# saw_filter_pcb.net
KiCad netlist of a schematic drawn in Altium Designer
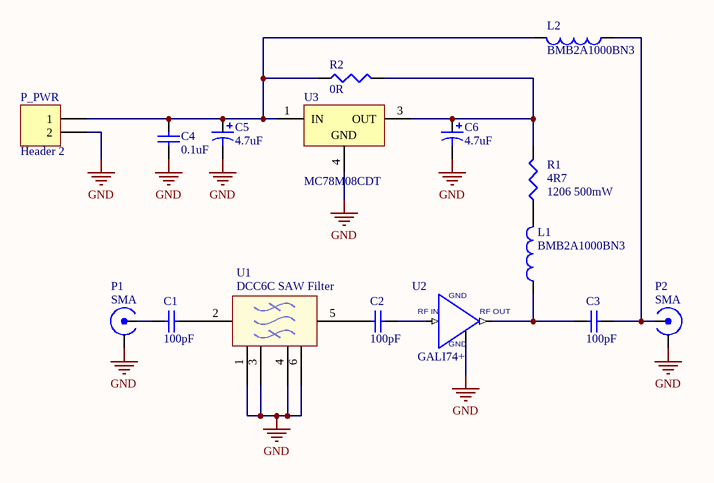
[diagram p0: saw_filter_pcb.SchDoc]

(export (version "E")
  (design (tool "Eeschema 10.0.6"))
  (components
    (comp (ref "C1")
      (value "100pF")
      (footprint "1608[0603]")
      (description "Capacitor (Semiconductor SIM Model)")
      (fields (field (name "Comment") "Cap Semi") (field (name "PUBLISHER") "Altium Limited"))
      (libsource (lib "Miscellaneous Devices") (part "Cap Semi"))
    )
    (comp (ref "C2")
      (value "100pF")
      (footprint "1608[0603]")
      (description "Capacitor (Semiconductor SIM Model)")
      (fields (field (name "Comment") "Cap Semi") (field (name "PUBLISHER") "Altium Limited"))
      (libsource (lib "Miscellaneous Devices") (part "Cap Semi"))
    )
    (comp (ref "C3")
      (value "100pF")
      (footprint "1608[0603]")
      (description "Capacitor (Semiconductor SIM Model)")
      (fields (field (name "Comment") "Cap Semi") (field (name "PUBLISHER") "Altium Limited"))
      (libsource (lib "Miscellaneous Devices") (part "Cap Semi"))
    )
    (comp (ref "C4")
      (value "0.1uF")
      (footprint "1608[0603]")
      (description "Capacitor (Semiconductor SIM Model)")
      (fields (field (name "Comment") "Cap Semi") (field (name "PUBLISHER") "Altium Limited"))
      (libsource (lib "Miscellaneous Devices") (part "Cap Semi"))
    )
    (comp (ref "C5")
      (value "4.7uF")
      (footprint "C0805")
      (description "Polarized Capacitor (Surface Mount)")
      (fields (field (name "Comment") "Cap Pol3") (field (name "PUBLISHER") "Altium Limited"))
      (libsource (lib "Miscellaneous Devices") (part "Cap Pol3"))
    )
    (comp (ref "C6")
      (value "4.7uF")
      (footprint "C0805")
      (description "Polarized Capacitor (Surface Mount)")
      (fields (field (name "Comment") "Cap Pol3") (field (name "PUBLISHER") "Altium Limited"))
      (libsource (lib "Miscellaneous Devices") (part "Cap Pol3"))
    )
    (comp (ref "L1")
      (value "BMB2A1000BN3")
      (footprint "6-0805_N")
      (description "Inductor")
      (fields (field (name "PUBLISHER") "Altium Limited"))
      (libsource (lib "Miscellaneous Devices") (part "Inductor"))
    )
    (comp (ref "L2")
      (value "BMB2A1000BN3")
      (footprint "6-0805_N")
      (description "Inductor")
      (fields (field (name "PUBLISHER") "Altium Limited"))
      (libsource (lib "Miscellaneous Devices") (part "Inductor"))
    )
    (comp (ref "P1")
      (value "SMA")
      (footprint "SMA_EDGE")
      (description "Power Connector")
      (fields (field (name "Comment") "SMA Con"))
      (libsource (lib "saw_filter_lib") (part "SMA Con"))
    )
    (comp (ref "P2")
      (value "SMA")
      (footprint "SMA_EDGE")
      (description "Power Connector")
      (fields (field (name "Comment") "SMA Con"))
      (libsource (lib "") (part "SMA Con_1"))
    )
    (comp (ref "P_PWR")
      (value "Header 2")
      (footprint "HDR1X2")
      (description "Header, 2-Pin")
      (fields (field (name "PUBLISHER") "Altium Limited"))
      (libsource (lib "Miscellaneous Connectors") (part "Header 2"))
    )
    (comp (ref "R1")
      (value "1206 500mW")
      (footprint "C1206")
      (description "Resistor")
      (fields (field (name "ALTIUM_VALUE") "4R7") (field (name "PUBLISHER") "Altium Limited"))
      (libsource (lib "Miscellaneous Devices") (part "Res3"))
    )
    (comp (ref "R2")
      (value "0R")
      (footprint "J1-0603")
      (description "Resistor")
      (fields (field (name "Comment") "Res3") (field (name "PUBLISHER") "Altium Limited"))
      (libsource (lib "Miscellaneous Devices") (part "Res3"))
    )
    (comp (ref "U1")
      (value "DCC6C SAW Filter")
      (footprint "DCC6C")
      (libsource (lib "saw_filter_lib") (part "DCC6C SAW Filter"))
    )
    (comp (ref "U2")
      (value "GALI74+")
      (footprint "DF782")
      (libsource (lib "saw_filter_lib") (part "GALI74+"))
    )
    (comp (ref "U3")
      (value "MC78M08CDT")
      (footprint "MP04A_N")
      (description "Three-Terminal Medium Current Positive Voltage Regulator")
      (fields (field (name "PUBLISHER") "Altium Limited"))
      (libsource (lib "ON Semi Power Mgt Voltage Regulator") (part "MC78M08CDT"))
    )
  )
  (nets
    (net (code "1") (name "GND") (class "Default")
      (node (ref "C4") (pin "1") (pinfunction "1_1") (pintype "passive"))
      (node (ref "C5") (pin "2") (pinfunction "2_2") (pintype "passive"))
      (node (ref "C6") (pin "2") (pinfunction "2_2") (pintype "passive"))
      (node (ref "P1") (pin "2") (pinfunction "2_2") (pintype "passive"))
      (node (ref "P2") (pin "2") (pinfunction "2_2") (pintype "passive"))
      (node (ref "P_PWR") (pin "2") (pinfunction "2_2") (pintype "passive"))
      (node (ref "U1") (pin "1") (pinfunction "IN_1") (pintype "passive"))
      (node (ref "U1") (pin "3") (pinfunction "IN_3") (pintype "passive"))
      (node (ref "U1") (pin "4") (pinfunction "IN_4") (pintype "passive"))
      (node (ref "U1") (pin "6") (pinfunction "IN_6") (pintype "passive"))
      (node (ref "U2") (pin "2") (pinfunction "GND_2") (pintype "power_in"))
      (node (ref "U3") (pin "4") (pinfunction "GND_4") (pintype "power_in"))
    )
    (net (code "2") (name "Net-(C1-Pad1)") (class "Default")
      (node (ref "C1") (pin "1") (pinfunction "1_1") (pintype "passive"))
      (node (ref "P1") (pin "1") (pinfunction "1_1") (pintype "passive"))
    )
    (net (code "3") (name "Net-(C1-Pad2)") (class "Default")
      (node (ref "C1") (pin "2") (pinfunction "2_2") (pintype "passive"))
      (node (ref "U1") (pin "2") (pinfunction "IN_2") (pintype "passive"))
    )
    (net (code "4") (name "Net-(C2-Pad1)") (class "Default")
      (node (ref "C2") (pin "1") (pinfunction "1_1") (pintype "passive"))
      (node (ref "U1") (pin "5") (pinfunction "5_5") (pintype "passive"))
    )
    (net (code "5") (name "Net-(C3-Pad2)") (class "Default")
      (node (ref "C3") (pin "2") (pinfunction "2_2") (pintype "passive"))
      (node (ref "L2") (pin "1") (pinfunction "1_1") (pintype "passive"))
      (node (ref "P2") (pin "1") (pinfunction "1_1") (pintype "passive"))
    )
    (net (code "6") (name "Net-(L1-Pad2)") (class "Default")
      (node (ref "L1") (pin "2") (pinfunction "2_2") (pintype "passive"))
      (node (ref "R1") (pin "1") (pinfunction "1_1") (pintype "passive"))
    )
    (net (code "7") (name "Net-(U2-RF-IN)") (class "Default")
      (node (ref "C2") (pin "2") (pinfunction "2_2") (pintype "passive"))
      (node (ref "U2") (pin "1") (pinfunction "RF-IN_1") (pintype "input"))
    )
    (net (code "8") (name "Net-(U2-RF-OUT)") (class "Default")
      (node (ref "C3") (pin "1") (pinfunction "1_1") (pintype "passive"))
      (node (ref "L1") (pin "1") (pinfunction "1_1") (pintype "passive"))
      (node (ref "U2") (pin "3") (pinfunction "RF-OUT_3") (pintype "output"))
    )
    (net (code "9") (name "Net-(U3-IN)") (class "Default")
      (node (ref "C4") (pin "2") (pinfunction "2_2") (pintype "passive"))
      (node (ref "C5") (pin "1") (pinfunction "1_1") (pintype "passive"))
      (node (ref "L2") (pin "2") (pinfunction "2_2") (pintype "passive"))
      (node (ref "P_PWR") (pin "1") (pinfunction "1_1") (pintype "passive"))
      (node (ref "R2") (pin "1") (pinfunction "1_1") (pintype "passive"))
      (node (ref "U3") (pin "1") (pinfunction "IN_1") (pintype "power_in"))
    )
    (net (code "10") (name "Net-(U3-OUT)") (class "Default")
      (node (ref "C6") (pin "1") (pinfunction "1_1") (pintype "passive"))
      (node (ref "R1") (pin "2") (pinfunction "2_2") (pintype "passive"))
      (node (ref "R2") (pin "2") (pinfunction "2_2") (pintype "passive"))
      (node (ref "U3") (pin "3") (pinfunction "OUT_3") (pintype "power_in"))
    )
  )
)
